# SmartHome.net
KiCad netlist of a schematic drawn in Altium Designer
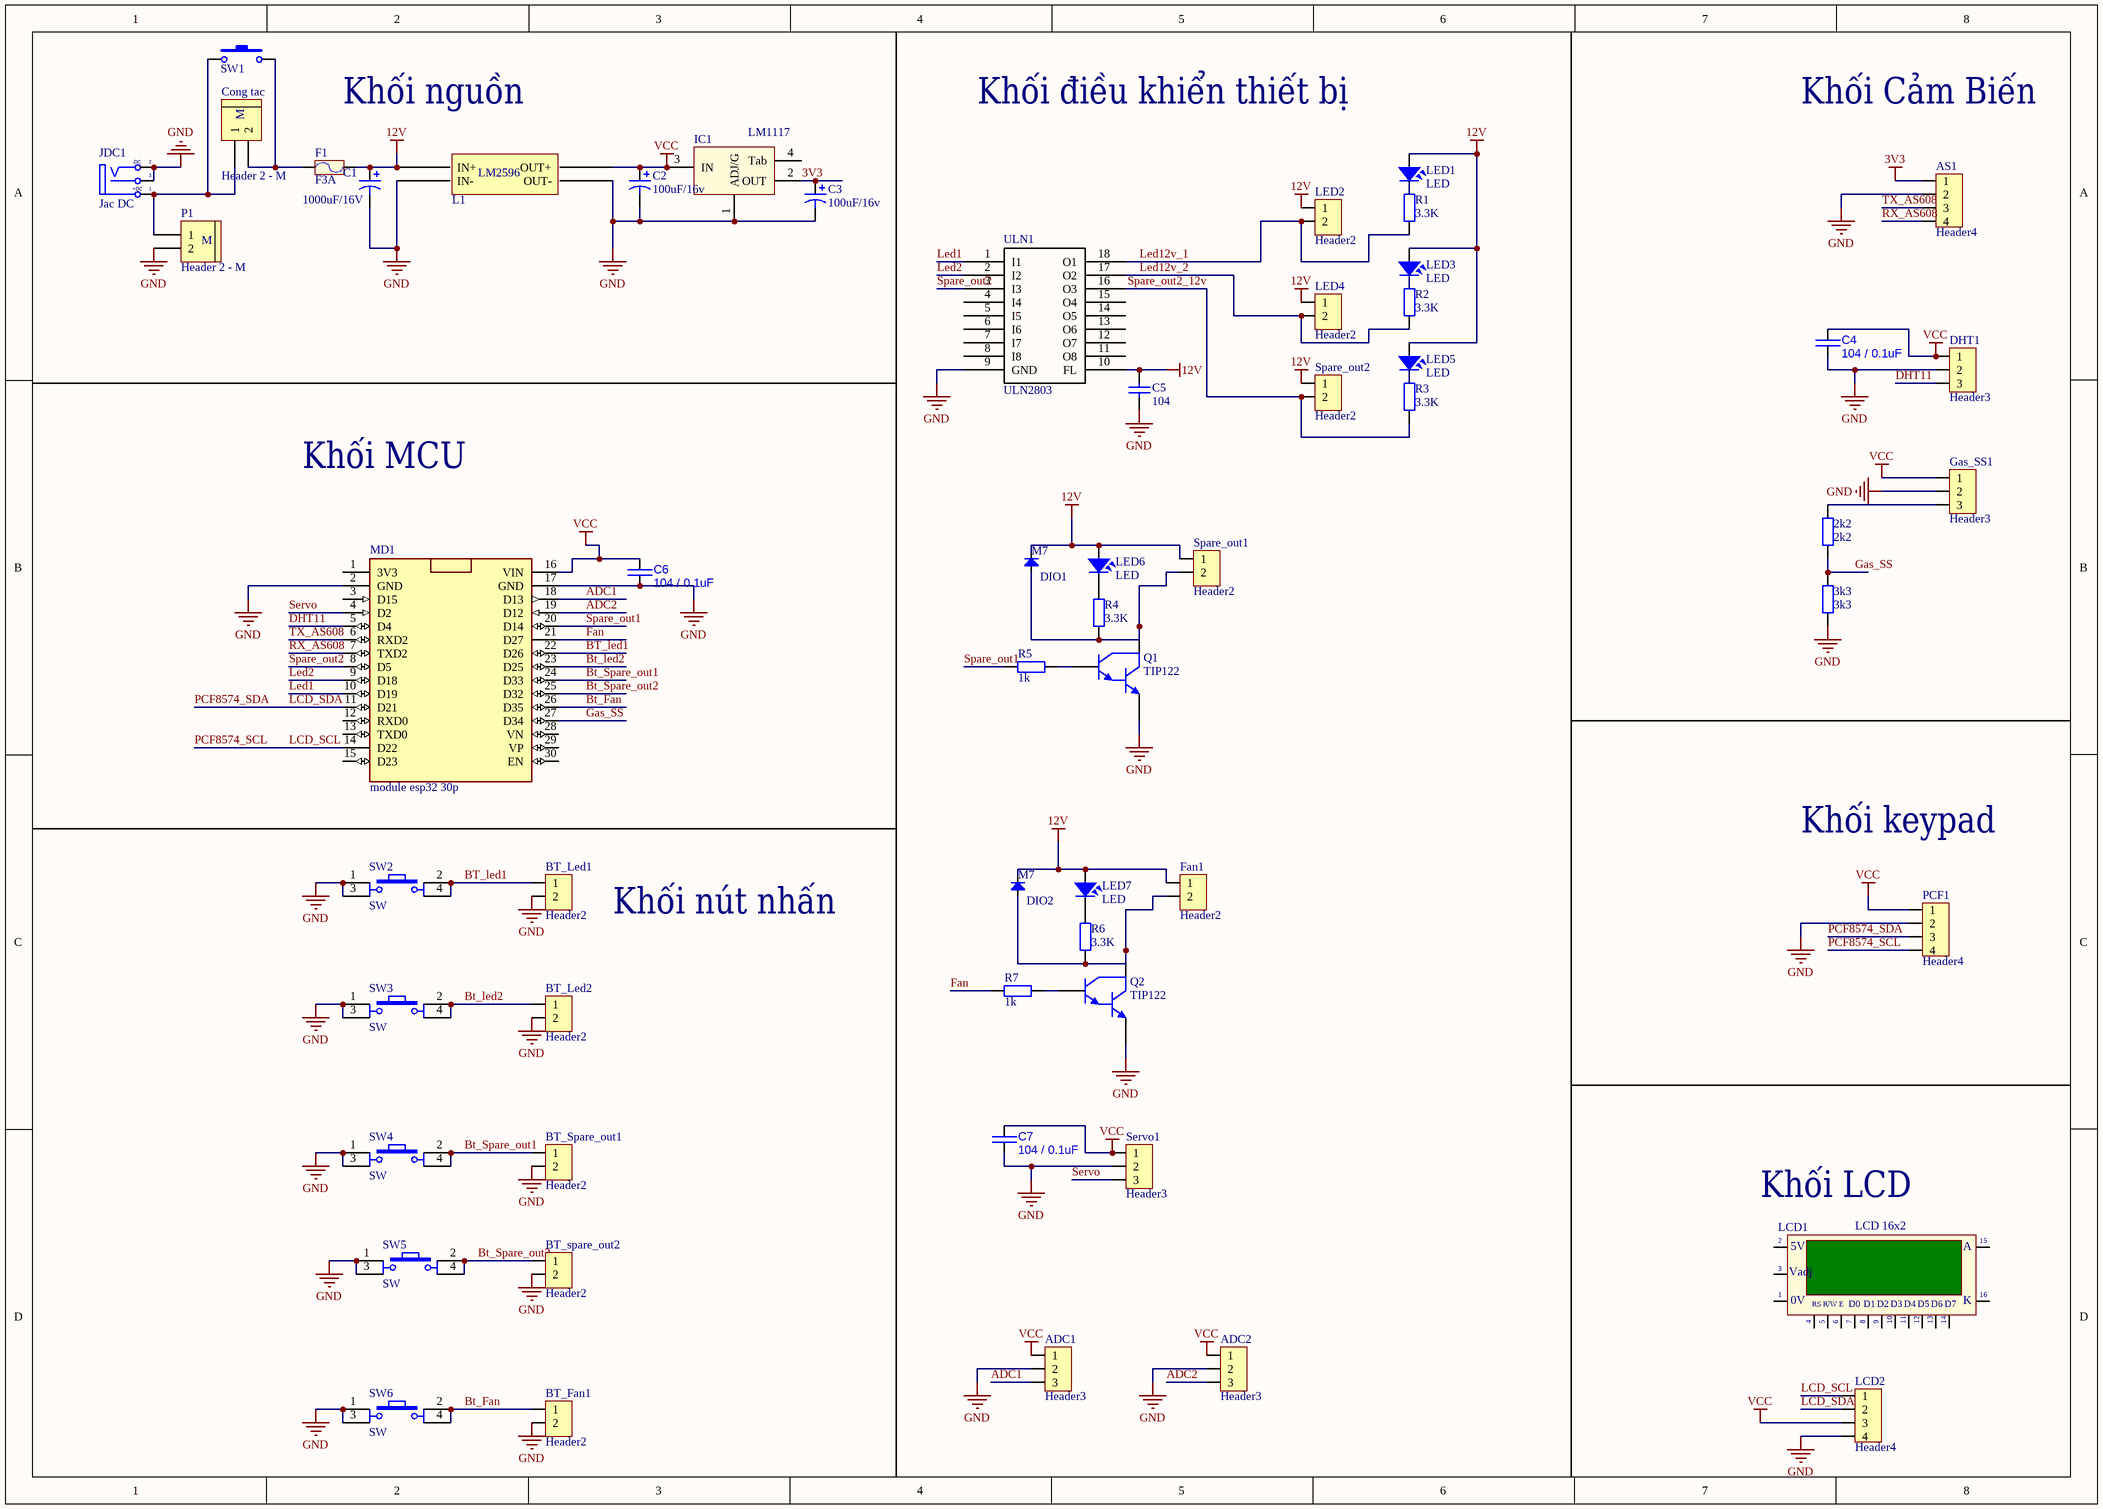
[diagram p0: SmartHome.SchDoc]

(export (version "E")
  (design (tool "Eeschema 10.0.6"))
  (components
    (comp (ref "2k2")
      (value "2k2")
      (footprint "DIEN TRO 0805")
      (description "Resistor SMD 0805")
      (fields (field (name "PUBLISHER") "Altium Limited"))
      (libsource (lib "My Library (1)") (part "R0805"))
    )
    (comp (ref "3k3")
      (value "3k3")
      (footprint "DIEN TRO 0805")
      (description "Resistor SMD 0805")
      (fields (field (name "PUBLISHER") "Altium Limited"))
      (libsource (lib "My Library (1)") (part "R0805"))
    )
    (comp (ref "ADC1")
      (value "Header3")
      (footprint "Header3")
      (description "Header IDC, 3 x 1 Pin Vertical 2.54mm Pitch (Non-Boxed, Male)")
      (fields
        (field (name "MANUFACTURER") "Würth Elektronik eiSos GmbH")
        (field (name "PARTNO") "613002143121")
        (field (name "CREATED BY") "Karrer Zheng")
      )
      (libsource (lib "My Library") (part "Header3"))
    )
    (comp (ref "ADC2")
      (value "Header3")
      (footprint "Header3")
      (description "Header IDC, 3 x 1 Pin Vertical 2.54mm Pitch (Non-Boxed, Male)")
      (fields
        (field (name "MANUFACTURER") "Würth Elektronik eiSos GmbH")
        (field (name "PARTNO") "613002143121")
        (field (name "CREATED BY") "Karrer Zheng")
      )
      (libsource (lib "My Library") (part "Header3"))
    )
    (comp (ref "AS1")
      (value "Header4")
      (footprint "Header4")
      (description "Header IDC, 4 x 1 Pin Vertical 2.54mm Pitch (Non-Boxed, Male)")
      (fields
        (field (name "MANUFACTURER") "Würth Elektronik eiSos GmbH")
        (field (name "PARTNO") "613002143121")
        (field (name "CREATED BY") "Karrer Zheng")
      )
      (libsource (lib "My Library") (part "Header4"))
    )
    (comp (ref "BT_Fan1")
      (value "Header2")
      (footprint "Header2")
      (description "Header IDC, 2 x 1 Pin Vertical 2.54mm Pitch (Non-Boxed, Male)")
      (fields
        (field (name "MANUFACTURER") "Würth Elektronik eiSos GmbH")
        (field (name "PARTNO") "613002143121")
        (field (name "CREATED BY") "Karrer Zheng")
      )
      (libsource (lib "My Library") (part "Header2"))
    )
    (comp (ref "BT_Led1")
      (value "Header2")
      (footprint "Header2")
      (description "Header IDC, 2 x 1 Pin Vertical 2.54mm Pitch (Non-Boxed, Male)")
      (fields
        (field (name "MANUFACTURER") "Würth Elektronik eiSos GmbH")
        (field (name "PARTNO") "613002143121")
        (field (name "CREATED BY") "Karrer Zheng")
      )
      (libsource (lib "My Library") (part "Header2"))
    )
    (comp (ref "BT_Led2")
      (value "Header2")
      (footprint "Header2")
      (description "Header IDC, 2 x 1 Pin Vertical 2.54mm Pitch (Non-Boxed, Male)")
      (fields
        (field (name "MANUFACTURER") "Würth Elektronik eiSos GmbH")
        (field (name "PARTNO") "613002143121")
        (field (name "CREATED BY") "Karrer Zheng")
      )
      (libsource (lib "My Library") (part "Header2"))
    )
    (comp (ref "BT_Spare_out1")
      (value "Header2")
      (footprint "Header2")
      (description "Header IDC, 2 x 1 Pin Vertical 2.54mm Pitch (Non-Boxed, Male)")
      (fields
        (field (name "MANUFACTURER") "Würth Elektronik eiSos GmbH")
        (field (name "PARTNO") "613002143121")
        (field (name "CREATED BY") "Karrer Zheng")
      )
      (libsource (lib "My Library") (part "Header2"))
    )
    (comp (ref "BT_spare_out2")
      (value "Header2")
      (footprint "Header2")
      (description "Header IDC, 2 x 1 Pin Vertical 2.54mm Pitch (Non-Boxed, Male)")
      (fields
        (field (name "MANUFACTURER") "Würth Elektronik eiSos GmbH")
        (field (name "PARTNO") "613002143121")
        (field (name "CREATED BY") "Karrer Zheng")
      )
      (libsource (lib "My Library") (part "Header2"))
    )
    (comp (ref "C1")
      (value "1000uF/16V")
      (footprint "C10mm")
      (description "Polarized Capacitor (Axial)")
      (fields (field (name "PUBLISHER") "Altium Limited"))
      (libsource (lib "My Library") (part "Cap Pol 12mm"))
    )
    (comp (ref "C2")
      (value "100uF/16v")
      (footprint "C5mm")
      (description "Polarized Capacitor (Axial)")
      (fields (field (name "PUBLISHER") "Altium Limited"))
      (libsource (lib "My Library") (part "Cap Pol 5mm"))
    )
    (comp (ref "C3")
      (value "100uF/16v")
      (footprint "C5mm")
      (description "Polarized Capacitor (Axial)")
      (fields (field (name "PUBLISHER") "Altium Limited"))
      (libsource (lib "My Library") (part "Cap Pol 5mm"))
    )
    (comp (ref "C4")
      (value "104 / 0.1uF")
      (footprint "CAP_0805")
      (description "Capacitor SMD Cer 1.8nF 10% 50V X7R 0805")
      (fields (field (name "TOLERANCE") "±10%") (field (name "Comment") "approved sub OK"))
      (libsource (lib "My library altium") (part "CAP C_0805"))
    )
    (comp (ref "C5")
      (value "104")
      (footprint "C0805")
      (description "Capacitor")
      (fields (field (name "PUBLISHER") "Altium Limited"))
      (libsource (lib "My Library") (part "CapSMD"))
    )
    (comp (ref "C6")
      (value "104 / 0.1uF")
      (footprint "CAP_0805")
      (description "Capacitor SMD Cer 1.8nF 10% 50V X7R 0805")
      (fields (field (name "TOLERANCE") "±10%") (field (name "Comment") "approved sub OK"))
      (libsource (lib "My library altium") (part "CAP C_0805"))
    )
    (comp (ref "C7")
      (value "104 / 0.1uF")
      (footprint "CAP_0805")
      (description "Capacitor SMD Cer 1.8nF 10% 50V X7R 0805")
      (fields (field (name "TOLERANCE") "±10%") (field (name "Comment") "approved sub OK"))
      (libsource (lib "My library altium") (part "CAP C_0805"))
    )
    (comp (ref "Cong tac")
      (value "Header 2 - M")
      (footprint "Medium - Header 2")
      (description "Header, 2-Pin, Medium")
      (fields (field (name "PUBLISHER") "Altium Limited"))
      (libsource (lib "My Library") (part "Header 2 - M"))
    )
    (comp (ref "DHT1")
      (value "Header3")
      (footprint "Header3")
      (description "Header IDC, 3 x 1 Pin Vertical 2.54mm Pitch (Non-Boxed, Male)")
      (fields
        (field (name "MANUFACTURER") "Würth Elektronik eiSos GmbH")
        (field (name "PARTNO") "613002143121")
        (field (name "CREATED BY") "Karrer Zheng")
      )
      (libsource (lib "My Library") (part "Header3"))
    )
    (comp (ref "DIO1")
      (value "M7")
      (footprint "DIO-SMD-106")
      (description "Default Diode")
      (fields (field (name "PUBLISHER") "Altium Limited"))
      (libsource (lib "My Library (1)") (part "Diode SMD"))
    )
    (comp (ref "DIO2")
      (value "M7")
      (footprint "DIO-SMD-106")
      (description "Default Diode")
      (fields (field (name "PUBLISHER") "Altium Limited"))
      (libsource (lib "My Library (1)") (part "Diode SMD"))
    )
    (comp (ref "F1")
      (value "F3A")
      (footprint "Fuse")
      (description "Fuse")
      (fields (field (name "DESIGNED BY") "VanDungEvn"))
      (libsource (lib "My Library") (part "Fuse"))
    )
    (comp (ref "Fan1")
      (value "Header2")
      (footprint "Header2")
      (description "Header IDC, 2 x 1 Pin Vertical 2.54mm Pitch (Non-Boxed, Male)")
      (fields
        (field (name "MANUFACTURER") "Würth Elektronik eiSos GmbH")
        (field (name "PARTNO") "613002143121")
        (field (name "CREATED BY") "Karrer Zheng")
      )
      (libsource (lib "My Library") (part "Header2"))
    )
    (comp (ref "Gas_SS1")
      (value "Header3")
      (footprint "Header3")
      (description "Header IDC, 3 x 1 Pin Vertical 2.54mm Pitch (Non-Boxed, Male)")
      (fields
        (field (name "MANUFACTURER") "Würth Elektronik eiSos GmbH")
        (field (name "PARTNO") "613002143121")
        (field (name "CREATED BY") "Karrer Zheng")
      )
      (libsource (lib "My Library") (part "Header3"))
    )
    (comp (ref "IC1")
      (value "LM1117")
      (footprint "SOT223-4N")
      (description "3v3")
      (libsource (lib "My Library") (part "LM1117"))
    )
    (comp (ref "JDC1")
      (value "Jac DC")
      (footprint "DC-IN")
      (description "Jac DC input")
      (libsource (lib "My Library") (part "DCIN"))
    )
    (comp (ref "L1")
      (value "BUCK_LM2596")
      (footprint "BUCK_LM2596")
      (libsource (lib "BUCK_LM2596_Sch") (part "BUCK_LM2596"))
    )
    (comp (ref "LCD1")
      (value "LCD 16x2")
      (footprint "LCD16X2N")
      (libsource (lib "My library altium") (part "LCD"))
    )
    (comp (ref "LCD2")
      (value "Header4")
      (footprint "XH2.54M-4")
      (description "Header IDC, 4 x 1 Pin Vertical 2.54mm Pitch (Non-Boxed, Male)")
      (fields
        (field (name "MANUFACTURER") "Würth Elektronik eiSos GmbH")
        (field (name "PARTNO") "613002143121")
        (field (name "CREATED BY") "Karrer Zheng")
      )
      (libsource (lib "My Library") (part "Header4"))
    )
    (comp (ref "LED1")
      (value "LED")
      (footprint "LED-5 GRe")
      (description "LED Single colour Green and Red")
      (libsource (lib "My Library") (part "LED"))
    )
    (comp (ref "LED2")
      (value "Header2")
      (footprint "Header2")
      (description "Header IDC, 2 x 1 Pin Vertical 2.54mm Pitch (Non-Boxed, Male)")
      (fields
        (field (name "MANUFACTURER") "Würth Elektronik eiSos GmbH")
        (field (name "PARTNO") "613002143121")
        (field (name "CREATED BY") "Karrer Zheng")
      )
      (libsource (lib "My Library") (part "Header2"))
    )
    (comp (ref "LED3")
      (value "LED")
      (footprint "LED-5 GRe")
      (description "LED Single colour Green and Red")
      (libsource (lib "My Library") (part "LED"))
    )
    (comp (ref "LED4")
      (value "Header2")
      (footprint "Header2")
      (description "Header IDC, 2 x 1 Pin Vertical 2.54mm Pitch (Non-Boxed, Male)")
      (fields
        (field (name "MANUFACTURER") "Würth Elektronik eiSos GmbH")
        (field (name "PARTNO") "613002143121")
        (field (name "CREATED BY") "Karrer Zheng")
      )
      (libsource (lib "My Library") (part "Header2"))
    )
    (comp (ref "LED5")
      (value "LED")
      (footprint "LED-5 GRe")
      (description "LED Single colour Green and Red")
      (libsource (lib "My Library") (part "LED"))
    )
    (comp (ref "LED6")
      (value "LED")
      (footprint "LED-5 GRe")
      (description "LED Single colour Green and Red")
      (libsource (lib "My Library") (part "LED"))
    )
    (comp (ref "LED7")
      (value "LED")
      (footprint "LED-5 GRe")
      (description "LED Single colour Green and Red")
      (libsource (lib "My Library") (part "LED"))
    )
    (comp (ref "MD1")
      (value "module esp32 30p")
      (footprint "module esp32 30 pin")
      (libsource (lib "Chuong Engineer") (part "module esp32 30p"))
    )
    (comp (ref "P1")
      (value "Header 2 - M")
      (footprint "Medium - Header 2")
      (description "Header, 2-Pin, Medium")
      (fields (field (name "PUBLISHER") "Altium Limited"))
      (libsource (lib "") (part "Header 2 - M_1"))
    )
    (comp (ref "PCF1")
      (value "Header4")
      (footprint "XH2.54M-4")
      (description "Header IDC, 4 x 1 Pin Vertical 2.54mm Pitch (Non-Boxed, Male)")
      (fields
        (field (name "MANUFACTURER") "Würth Elektronik eiSos GmbH")
        (field (name "PARTNO") "613002143121")
        (field (name "CREATED BY") "Karrer Zheng")
      )
      (libsource (lib "My Library") (part "Header4"))
    )
    (comp (ref "Q1")
      (value "TIP122")
      (footprint "QTO-220")
      (description "Darlington Silicon Power NPN Transistor, 8 Amp, 100 Volts and 65 Watts")
      (libsource (lib "My Library (1)") (part "TIP122"))
    )
    (comp (ref "Q2")
      (value "TIP122")
      (footprint "QTO-220")
      (description "Darlington Silicon Power NPN Transistor, 8 Amp, 100 Volts and 65 Watts")
      (libsource (lib "My Library (1)") (part "TIP122"))
    )
    (comp (ref "R1")
      (value "3.3K")
      (footprint "DIEN TRO 0805")
      (description "Resistor SMD 0805")
      (fields (field (name "PUBLISHER") "Altium Limited"))
      (libsource (lib "My Library (1)") (part "R0805"))
    )
    (comp (ref "R2")
      (value "3.3K")
      (footprint "DIEN TRO 0805")
      (description "Resistor SMD 0805")
      (fields (field (name "PUBLISHER") "Altium Limited"))
      (libsource (lib "My Library (1)") (part "R0805"))
    )
    (comp (ref "R3")
      (value "3.3K")
      (footprint "DIEN TRO 0805")
      (description "Resistor SMD 0805")
      (fields (field (name "PUBLISHER") "Altium Limited"))
      (libsource (lib "My Library (1)") (part "R0805"))
    )
    (comp (ref "R4")
      (value "3.3K")
      (footprint "DIEN TRO 0805")
      (description "Resistor SMD 0805")
      (fields (field (name "PUBLISHER") "Altium Limited"))
      (libsource (lib "My Library (1)") (part "R0805"))
    )
    (comp (ref "R5")
      (value "1k")
      (footprint "DIEN TRO 0805")
      (description "Resistor SMD 0805")
      (fields (field (name "PUBLISHER") "Altium Limited"))
      (libsource (lib "") (part "R0805_1"))
    )
    (comp (ref "R6")
      (value "3.3K")
      (footprint "DIEN TRO 0805")
      (description "Resistor SMD 0805")
      (fields (field (name "PUBLISHER") "Altium Limited"))
      (libsource (lib "My Library (1)") (part "R0805"))
    )
    (comp (ref "R7")
      (value "1k")
      (footprint "DIEN TRO 0805")
      (description "Resistor SMD 0805")
      (fields (field (name "PUBLISHER") "Altium Limited"))
      (libsource (lib "") (part "R0805_1"))
    )
    (comp (ref "Servo1")
      (value "Header3")
      (footprint "Header3")
      (description "Header IDC, 3 x 1 Pin Vertical 2.54mm Pitch (Non-Boxed, Male)")
      (fields
        (field (name "MANUFACTURER") "Würth Elektronik eiSos GmbH")
        (field (name "PARTNO") "613002143121")
        (field (name "CREATED BY") "Karrer Zheng")
      )
      (libsource (lib "My Library") (part "Header3"))
    )
    (comp (ref "Spare_out1")
      (value "Header2")
      (footprint "Header2")
      (description "Header IDC, 2 x 1 Pin Vertical 2.54mm Pitch (Non-Boxed, Male)")
      (fields
        (field (name "MANUFACTURER") "Würth Elektronik eiSos GmbH")
        (field (name "PARTNO") "613002143121")
        (field (name "CREATED BY") "Karrer Zheng")
      )
      (libsource (lib "My Library") (part "Header2"))
    )
    (comp (ref "Spare_out2")
      (value "Header2")
      (footprint "Header2")
      (description "Header IDC, 2 x 1 Pin Vertical 2.54mm Pitch (Non-Boxed, Male)")
      (fields
        (field (name "MANUFACTURER") "Würth Elektronik eiSos GmbH")
        (field (name "PARTNO") "613002143121")
        (field (name "CREATED BY") "Karrer Zheng")
      )
      (libsource (lib "My Library") (part "Header2"))
    )
    (comp (ref "SW1")
      (value "KCD01-11_SWITCH")
      (footprint "KCD01-11")
      (description "Nut Nhan 2 Chan SMD 3x6x2.5")
      (libsource (lib "KS Chuong") (part "KCD01-11_SWITCH"))
    )
    (comp (ref "SW2")
      (value "SW")
      (footprint "SW4")
      (description "Switch button 4 pin")
      (libsource (lib "My Library (1)") (part "SW4"))
    )
    (comp (ref "SW3")
      (value "SW")
      (footprint "SW4")
      (description "Switch button 4 pin")
      (libsource (lib "My Library (1)") (part "SW4"))
    )
    (comp (ref "SW4")
      (value "SW")
      (footprint "SW4")
      (description "Switch button 4 pin")
      (libsource (lib "My Library (1)") (part "SW4"))
    )
    (comp (ref "SW5")
      (value "SW")
      (footprint "SW4")
      (description "Switch button 4 pin")
      (libsource (lib "My Library (1)") (part "SW4"))
    )
    (comp (ref "SW6")
      (value "SW")
      (footprint "SW4")
      (description "Switch button 4 pin")
      (libsource (lib "My Library (1)") (part "SW4"))
    )
    (comp (ref "ULN1")
      (value "ULN2803")
      (footprint "DIP18/W0.3")
      (description "OCTAL HIGH CURRENT DRIVER")
      (fields
        (field (name "MANUFACTURER") "Texas Instruments")
        (field (name "MANUFACTURER PART NUMBER") "ULN2803ADWR")
      )
      (libsource (lib "My Library") (part "ULN2803"))
    )
  )
  (nets
    (net (code "1") (name "/ADC1") (class "Default")
      (node (ref "ADC1") (pin "3") (pinfunction "3_3") (pintype "passive"))
      (node (ref "MD1") (pin "18") (pinfunction "D13_18") (pintype "output"))
    )
    (net (code "2") (name "/ADC2") (class "Default")
      (node (ref "ADC2") (pin "3") (pinfunction "3_3") (pintype "passive"))
      (node (ref "MD1") (pin "19") (pinfunction "D12_19") (pintype "input"))
    )
    (net (code "3") (name "/BT_led1") (class "Default")
      (node (ref "BT_Led1") (pin "1") (pinfunction "1_1") (pintype "passive"))
      (node (ref "MD1") (pin "22") (pinfunction "D26_22") (pintype "bidirectional"))
      (node (ref "SW2") (pin "2") (pintype "passive"))
      (node (ref "SW2") (pin "4") (pintype "passive"))
    )
    (net (code "4") (name "/Bt_Fan") (class "Default")
      (node (ref "BT_Fan1") (pin "1") (pinfunction "1_1") (pintype "passive"))
      (node (ref "MD1") (pin "26") (pinfunction "D35_26") (pintype "bidirectional"))
      (node (ref "SW6") (pin "2") (pintype "passive"))
      (node (ref "SW6") (pin "4") (pintype "passive"))
    )
    (net (code "5") (name "/Bt_Spare_out1") (class "Default")
      (node (ref "BT_Spare_out1") (pin "1") (pinfunction "1_1") (pintype "passive"))
      (node (ref "MD1") (pin "24") (pinfunction "D33_24") (pintype "bidirectional"))
      (node (ref "SW4") (pin "2") (pintype "passive"))
      (node (ref "SW4") (pin "4") (pintype "passive"))
    )
    (net (code "6") (name "/Bt_Spare_out2") (class "Default")
      (node (ref "BT_spare_out2") (pin "1") (pinfunction "1_1") (pintype "passive"))
      (node (ref "MD1") (pin "25") (pinfunction "D32_25") (pintype "bidirectional"))
      (node (ref "SW5") (pin "2") (pintype "passive"))
      (node (ref "SW5") (pin "4") (pintype "passive"))
    )
    (net (code "7") (name "/Bt_led2") (class "Default")
      (node (ref "BT_Led2") (pin "1") (pinfunction "1_1") (pintype "passive"))
      (node (ref "MD1") (pin "23") (pinfunction "D25_23") (pintype "bidirectional"))
      (node (ref "SW3") (pin "2") (pintype "passive"))
      (node (ref "SW3") (pin "4") (pintype "passive"))
    )
    (net (code "8") (name "/DHT11") (class "Default")
      (node (ref "DHT1") (pin "3") (pinfunction "3_3") (pintype "passive"))
      (node (ref "MD1") (pin "5") (pinfunction "D4_5") (pintype "bidirectional"))
    )
    (net (code "9") (name "/Fan") (class "Default")
      (node (ref "MD1") (pin "21") (pinfunction "D27_21") (pintype "power_in"))
      (node (ref "R7") (pin "2") (pinfunction "2_2") (pintype "passive"))
    )
    (net (code "10") (name "/Gas_SS") (class "Default")
      (node (ref "2k2") (pin "2") (pinfunction "2_2") (pintype "passive"))
      (node (ref "3k3") (pin "1") (pinfunction "1_1") (pintype "passive"))
      (node (ref "MD1") (pin "27") (pinfunction "D34_27") (pintype "bidirectional"))
    )
    (net (code "11") (name "/LCD_SCL") (class "Default")
      (node (ref "LCD2") (pin "1") (pinfunction "1_1") (pintype "passive"))
      (node (ref "MD1") (pin "14") (pinfunction "D22_14") (pintype "power_in"))
      (node (ref "PCF1") (pin "4") (pinfunction "4_4") (pintype "passive"))
    )
    (net (code "12") (name "/LCD_SDA") (class "Default")
      (node (ref "LCD2") (pin "2") (pinfunction "2_2") (pintype "passive"))
      (node (ref "MD1") (pin "11") (pinfunction "D21_11") (pintype "bidirectional"))
      (node (ref "PCF1") (pin "3") (pinfunction "3_3") (pintype "passive"))
    )
    (net (code "13") (name "/Led1") (class "Default")
      (node (ref "MD1") (pin "10") (pinfunction "D19_10") (pintype "bidirectional"))
      (node (ref "ULN1") (pin "1") (pinfunction "I1_1") (pintype "passive"))
    )
    (net (code "14") (name "/Led2") (class "Default")
      (node (ref "MD1") (pin "9") (pinfunction "D18_9") (pintype "bidirectional"))
      (node (ref "ULN1") (pin "2") (pinfunction "I2_2") (pintype "passive"))
    )
    (net (code "15") (name "/Led12v_1") (class "Default")
      (node (ref "LED2") (pin "2") (pinfunction "2_2") (pintype "passive"))
      (node (ref "R1") (pin "2") (pinfunction "2_2") (pintype "passive"))
      (node (ref "ULN1") (pin "18") (pinfunction "O1_18") (pintype "passive"))
    )
    (net (code "16") (name "/Led12v_2") (class "Default")
      (node (ref "LED4") (pin "2") (pinfunction "2_2") (pintype "passive"))
      (node (ref "R2") (pin "2") (pinfunction "2_2") (pintype "passive"))
      (node (ref "ULN1") (pin "17") (pinfunction "O2_17") (pintype "passive"))
    )
    (net (code "17") (name "/RX_AS608") (class "Default")
      (node (ref "AS1") (pin "4") (pinfunction "4_4") (pintype "passive"))
      (node (ref "MD1") (pin "7") (pinfunction "TXD2_7") (pintype "bidirectional"))
    )
    (net (code "18") (name "/Servo") (class "Default")
      (node (ref "MD1") (pin "4") (pinfunction "D2_4") (pintype "input"))
      (node (ref "Servo1") (pin "3") (pinfunction "3_3") (pintype "passive"))
    )
    (net (code "19") (name "/Spare_out1") (class "Default")
      (node (ref "MD1") (pin "20") (pinfunction "D14_20") (pintype "bidirectional"))
      (node (ref "R5") (pin "2") (pinfunction "2_2") (pintype "passive"))
    )
    (net (code "20") (name "/Spare_out2") (class "Default")
      (node (ref "MD1") (pin "8") (pinfunction "D5_8") (pintype "bidirectional"))
      (node (ref "ULN1") (pin "3") (pinfunction "I3_3") (pintype "passive"))
    )
    (net (code "21") (name "/Spare_out2_12v") (class "Default")
      (node (ref "R3") (pin "2") (pinfunction "2_2") (pintype "passive"))
      (node (ref "Spare_out2") (pin "2") (pinfunction "2_2") (pintype "passive"))
      (node (ref "ULN1") (pin "16") (pinfunction "O3_16") (pintype "passive"))
    )
    (net (code "22") (name "/TX_AS608") (class "Default")
      (node (ref "AS1") (pin "3") (pinfunction "3_3") (pintype "passive"))
      (node (ref "MD1") (pin "6") (pinfunction "RXD2_6") (pintype "bidirectional"))
    )
    (net (code "23") (name "3V3") (class "Default")
      (node (ref "AS1") (pin "1") (pinfunction "1_1") (pintype "passive"))
      (node (ref "C3") (pin "1") (pinfunction "1_1") (pintype "passive"))
      (node (ref "IC1") (pin "2") (pinfunction "OUT_2") (pintype "passive"))
    )
    (net (code "24") (name "12V") (class "Default")
      (node (ref "C1") (pin "1") (pinfunction "1_1") (pintype "passive"))
      (node (ref "C5") (pin "1") (pinfunction "1_1") (pintype "passive"))
      (node (ref "DIO1") (pin "2") (pinfunction "K_2") (pintype "passive"))
      (node (ref "DIO2") (pin "2") (pinfunction "K_2") (pintype "passive"))
      (node (ref "F1") (pin "2") (pinfunction "2_2") (pintype "passive"))
      (node (ref "Fan1") (pin "1") (pinfunction "1_1") (pintype "passive"))
      (node (ref "L1") (pin "1") (pinfunction "IN+_1") (pintype "passive"))
      (node (ref "LED1") (pin "1") (pinfunction "1_1") (pintype "passive"))
      (node (ref "LED2") (pin "1") (pinfunction "1_1") (pintype "passive"))
      (node (ref "LED3") (pin "1") (pinfunction "1_1") (pintype "passive"))
      (node (ref "LED4") (pin "1") (pinfunction "1_1") (pintype "passive"))
      (node (ref "LED5") (pin "1") (pinfunction "1_1") (pintype "passive"))
      (node (ref "LED6") (pin "1") (pinfunction "1_1") (pintype "passive"))
      (node (ref "LED7") (pin "1") (pinfunction "1_1") (pintype "passive"))
      (node (ref "Spare_out1") (pin "1") (pinfunction "1_1") (pintype "passive"))
      (node (ref "Spare_out2") (pin "1") (pinfunction "1_1") (pintype "passive"))
      (node (ref "ULN1") (pin "10") (pinfunction "FL_10") (pintype "passive"))
    )
    (net (code "25") (name "GND") (class "Default")
      (node (ref "3k3") (pin "2") (pinfunction "2_2") (pintype "passive"))
      (node (ref "ADC1") (pin "2") (pinfunction "2_2") (pintype "passive"))
      (node (ref "ADC2") (pin "2") (pinfunction "2_2") (pintype "passive"))
      (node (ref "AS1") (pin "2") (pinfunction "2_2") (pintype "passive"))
      (node (ref "BT_Fan1") (pin "2") (pinfunction "2_2") (pintype "passive"))
      (node (ref "BT_Led1") (pin "2") (pinfunction "2_2") (pintype "passive"))
      (node (ref "BT_Led2") (pin "2") (pinfunction "2_2") (pintype "passive"))
      (node (ref "BT_Spare_out1") (pin "2") (pinfunction "2_2") (pintype "passive"))
      (node (ref "BT_spare_out2") (pin "2") (pinfunction "2_2") (pintype "passive"))
      (node (ref "C1") (pin "2") (pinfunction "2_2") (pintype "passive"))
      (node (ref "C2") (pin "2") (pinfunction "2_2") (pintype "passive"))
      (node (ref "C3") (pin "2") (pinfunction "2_2") (pintype "passive"))
      (node (ref "C4") (pin "1") (pintype "passive"))
      (node (ref "C5") (pin "2") (pinfunction "2_2") (pintype "passive"))
      (node (ref "C6") (pin "1") (pintype "passive"))
      (node (ref "C7") (pin "1") (pintype "passive"))
      (node (ref "DHT1") (pin "2") (pinfunction "2_2") (pintype "passive"))
      (node (ref "Gas_SS1") (pin "2") (pinfunction "2_2") (pintype "passive"))
      (node (ref "IC1") (pin "1") (pinfunction "ADJ/G_1") (pintype "passive"))
      (node (ref "JDC1") (pin "2") (pinfunction "TN_2") (pintype "passive"))
      (node (ref "JDC1") (pin "3") (pinfunction "S_3") (pintype "power_in"))
      (node (ref "L1") (pin "2") (pinfunction "IN-_2") (pintype "passive"))
      (node (ref "L1") (pin "3") (pinfunction "OUT-_3") (pintype "passive"))
      (node (ref "LCD2") (pin "4") (pinfunction "4_4") (pintype "passive"))
      (node (ref "MD1") (pin "17") (pinfunction "GND_17") (pintype "power_in"))
      (node (ref "MD1") (pin "2") (pinfunction "GND_2") (pintype "power_in"))
      (node (ref "P1") (pin "2") (pinfunction "2_2") (pintype "passive"))
      (node (ref "PCF1") (pin "2") (pinfunction "2_2") (pintype "passive"))
      (node (ref "Q1") (pin "3") (pinfunction "E_3") (pintype "passive"))
      (node (ref "Q2") (pin "3") (pinfunction "E_3") (pintype "passive"))
      (node (ref "SW2") (pin "1") (pintype "passive"))
      (node (ref "SW2") (pin "3") (pintype "passive"))
      (node (ref "SW3") (pin "1") (pintype "passive"))
      (node (ref "SW3") (pin "3") (pintype "passive"))
      (node (ref "SW4") (pin "1") (pintype "passive"))
      (node (ref "SW4") (pin "3") (pintype "passive"))
      (node (ref "SW5") (pin "1") (pintype "passive"))
      (node (ref "SW5") (pin "3") (pintype "passive"))
      (node (ref "SW6") (pin "1") (pintype "passive"))
      (node (ref "SW6") (pin "3") (pintype "passive"))
      (node (ref "Servo1") (pin "2") (pinfunction "2_2") (pintype "passive"))
      (node (ref "ULN1") (pin "9") (pinfunction "GND_9") (pintype "passive"))
    )
    (net (code "26") (name "Net-(2k2-Pad1)") (class "Default")
      (node (ref "2k2") (pin "1") (pinfunction "1_1") (pintype "passive"))
      (node (ref "Gas_SS1") (pin "3") (pinfunction "3_3") (pintype "passive"))
    )
    (net (code "27") (name "Net-(Cong tac-Pad2)") (class "Default")
      (node (ref "Cong tac") (pin "2") (pinfunction "2_2") (pintype "passive"))
      (node (ref "F1") (pin "1") (pinfunction "1_1") (pintype "passive"))
      (node (ref "SW1") (pin "2") (pinfunction "2_2") (pintype "passive"))
    )
    (net (code "28") (name "Net-(DIO1-A)") (class "Default")
      (node (ref "DIO1") (pin "1") (pinfunction "A_1") (pintype "passive"))
      (node (ref "Q1") (pin "2") (pinfunction "C_2") (pintype "passive"))
      (node (ref "R4") (pin "2") (pinfunction "2_2") (pintype "passive"))
      (node (ref "Spare_out1") (pin "2") (pinfunction "2_2") (pintype "passive"))
    )
    (net (code "29") (name "Net-(DIO2-A)") (class "Default")
      (node (ref "DIO2") (pin "1") (pinfunction "A_1") (pintype "passive"))
      (node (ref "Fan1") (pin "2") (pinfunction "2_2") (pintype "passive"))
      (node (ref "Q2") (pin "2") (pinfunction "C_2") (pintype "passive"))
      (node (ref "R6") (pin "2") (pinfunction "2_2") (pintype "passive"))
    )
    (net (code "30") (name "Net-(JDC1-T)") (class "Default")
      (node (ref "Cong tac") (pin "1") (pinfunction "1_1") (pintype "passive"))
      (node (ref "JDC1") (pin "1") (pinfunction "T_1") (pintype "passive"))
      (node (ref "P1") (pin "1") (pinfunction "1_1") (pintype "passive"))
      (node (ref "SW1") (pin "1") (pinfunction "1_1") (pintype "passive"))
    )
    (net (code "31") (name "Net-(LED1-Pad2)") (class "Default")
      (node (ref "LED1") (pin "2") (pinfunction "2_2") (pintype "passive"))
      (node (ref "R1") (pin "1") (pinfunction "1_1") (pintype "passive"))
    )
    (net (code "32") (name "Net-(LED3-Pad2)") (class "Default")
      (node (ref "LED3") (pin "2") (pinfunction "2_2") (pintype "passive"))
      (node (ref "R2") (pin "1") (pinfunction "1_1") (pintype "passive"))
    )
    (net (code "33") (name "Net-(LED5-Pad2)") (class "Default")
      (node (ref "LED5") (pin "2") (pinfunction "2_2") (pintype "passive"))
      (node (ref "R3") (pin "1") (pinfunction "1_1") (pintype "passive"))
    )
    (net (code "34") (name "Net-(LED6-Pad2)") (class "Default")
      (node (ref "LED6") (pin "2") (pinfunction "2_2") (pintype "passive"))
      (node (ref "R4") (pin "1") (pinfunction "1_1") (pintype "passive"))
    )
    (net (code "35") (name "Net-(LED7-Pad2)") (class "Default")
      (node (ref "LED7") (pin "2") (pinfunction "2_2") (pintype "passive"))
      (node (ref "R6") (pin "1") (pinfunction "1_1") (pintype "passive"))
    )
    (net (code "36") (name "Net-(Q1-B)") (class "Default")
      (node (ref "Q1") (pin "1") (pinfunction "B_1") (pintype "passive"))
      (node (ref "R5") (pin "1") (pinfunction "1_1") (pintype "passive"))
    )
    (net (code "37") (name "Net-(Q2-B)") (class "Default")
      (node (ref "Q2") (pin "1") (pinfunction "B_1") (pintype "passive"))
      (node (ref "R7") (pin "1") (pinfunction "1_1") (pintype "passive"))
    )
    (net (code "38") (name "VCC") (class "Default")
      (node (ref "ADC1") (pin "1") (pinfunction "1_1") (pintype "passive"))
      (node (ref "ADC2") (pin "1") (pinfunction "1_1") (pintype "passive"))
      (node (ref "C2") (pin "1") (pinfunction "1_1") (pintype "passive"))
      (node (ref "C4") (pin "2") (pintype "passive"))
      (node (ref "C6") (pin "2") (pintype "passive"))
      (node (ref "C7") (pin "2") (pintype "passive"))
      (node (ref "DHT1") (pin "1") (pinfunction "1_1") (pintype "passive"))
      (node (ref "Gas_SS1") (pin "1") (pinfunction "1_1") (pintype "passive"))
      (node (ref "IC1") (pin "3") (pinfunction "IN_3") (pintype "passive"))
      (node (ref "L1") (pin "4") (pinfunction "OUT+_4") (pintype "passive"))
      (node (ref "LCD2") (pin "3") (pinfunction "3_3") (pintype "passive"))
      (node (ref "MD1") (pin "16") (pinfunction "VIN_16") (pintype "power_in"))
      (node (ref "PCF1") (pin "1") (pinfunction "1_1") (pintype "passive"))
      (node (ref "Servo1") (pin "1") (pinfunction "1_1") (pintype "passive"))
    )
    (net (code "39") (name "unconnected-(IC1-Tab-Pad4)") (class "Default")
      (node (ref "IC1") (pin "4") (pinfunction "Tab_4") (pintype "passive"))
    )
    (net (code "40") (name "unconnected-(LCD1-A-Pad15)") (class "Default")
      (node (ref "LCD1") (pin "15") (pinfunction "A_15") (pintype "passive"))
    )
    (net (code "41") (name "unconnected-(LCD1-D0-Pad7)") (class "Default")
      (node (ref "LCD1") (pin "7") (pinfunction "D0_7") (pintype "passive"))
    )
    (net (code "42") (name "unconnected-(LCD1-D1-Pad8)") (class "Default")
      (node (ref "LCD1") (pin "8") (pinfunction "D1_8") (pintype "passive"))
    )
    (net (code "43") (name "unconnected-(LCD1-D2-Pad9)") (class "Default")
      (node (ref "LCD1") (pin "9") (pinfunction "D2_9") (pintype "passive"))
    )
    (net (code "44") (name "unconnected-(LCD1-D3-Pad10)") (class "Default")
      (node (ref "LCD1") (pin "10") (pinfunction "D3_10") (pintype "passive"))
    )
    (net (code "45") (name "unconnected-(LCD1-D4-Pad11)") (class "Default")
      (node (ref "LCD1") (pin "11") (pinfunction "D4_11") (pintype "passive"))
    )
    (net (code "46") (name "unconnected-(LCD1-D5-Pad12)") (class "Default")
      (node (ref "LCD1") (pin "12") (pinfunction "D5_12") (pintype "passive"))
    )
    (net (code "47") (name "unconnected-(LCD1-D6-Pad13)") (class "Default")
      (node (ref "LCD1") (pin "13") (pinfunction "D6_13") (pintype "passive"))
    )
    (net (code "48") (name "unconnected-(LCD1-D7-Pad14)") (class "Default")
      (node (ref "LCD1") (pin "14") (pinfunction "D7_14") (pintype "passive"))
    )
    (net (code "49") (name "unconnected-(LCD1-GND-Pad1)") (class "Default")
      (node (ref "LCD1") (pin "1") (pinfunction "GND_1") (pintype "passive"))
    )
    (net (code "50") (name "unconnected-(LCD1-K-Pad16)") (class "Default")
      (node (ref "LCD1") (pin "16") (pinfunction "K_16") (pintype "passive"))
    )
    (net (code "51") (name "unconnected-(LCD1-RS-Pad4)") (class "Default")
      (node (ref "LCD1") (pin "4") (pinfunction "RS_4") (pintype "passive"))
    )
    (net (code "52") (name "unconnected-(LCD1-R{slash}~{W}-Pad5)") (class "Default")
      (node (ref "LCD1") (pin "5") (pinfunction "R/~{W}_5") (pintype "passive"))
    )
    (net (code "53") (name "unconnected-(LCD1-VAdj-Pad3)") (class "Default")
      (node (ref "LCD1") (pin "3") (pinfunction "VAdj_3") (pintype "passive"))
    )
    (net (code "54") (name "unconnected-(LCD1-VDD-Pad2)") (class "Default")
      (node (ref "LCD1") (pin "2") (pinfunction "VDD_2") (pintype "passive"))
    )
    (net (code "55") (name "unconnected-(LCD1-~{EN}-Pad6)") (class "Default")
      (node (ref "LCD1") (pin "6") (pinfunction "~{EN}_6") (pintype "passive"))
    )
    (net (code "56") (name "unconnected-(MD1-3V3-Pad1)") (class "Default")
      (node (ref "MD1") (pin "1") (pinfunction "3V3_1") (pintype "power_in"))
    )
    (net (code "57") (name "unconnected-(MD1-D15-Pad3)") (class "Default")
      (node (ref "MD1") (pin "3") (pinfunction "D15_3") (pintype "input"))
    )
    (net (code "58") (name "unconnected-(MD1-D23-Pad15)") (class "Default")
      (node (ref "MD1") (pin "15") (pinfunction "D23_15") (pintype "bidirectional"))
    )
    (net (code "59") (name "unconnected-(MD1-EN-Pad30)") (class "Default")
      (node (ref "MD1") (pin "30") (pinfunction "EN_30") (pintype "bidirectional"))
    )
    (net (code "60") (name "unconnected-(MD1-RXD0-Pad12)") (class "Default")
      (node (ref "MD1") (pin "12") (pinfunction "RXD0_12") (pintype "bidirectional"))
    )
    (net (code "61") (name "unconnected-(MD1-TXD0-Pad13)") (class "Default")
      (node (ref "MD1") (pin "13") (pinfunction "TXD0_13") (pintype "bidirectional"))
    )
    (net (code "62") (name "unconnected-(MD1-VN-Pad28)") (class "Default")
      (node (ref "MD1") (pin "28") (pinfunction "VN_28") (pintype "bidirectional"))
    )
    (net (code "63") (name "unconnected-(MD1-VP-Pad29)") (class "Default")
      (node (ref "MD1") (pin "29") (pinfunction "VP_29") (pintype "bidirectional"))
    )
    (net (code "64") (name "unconnected-(ULN1-I4-Pad4)") (class "Default")
      (node (ref "ULN1") (pin "4") (pinfunction "I4_4") (pintype "passive"))
    )
    (net (code "65") (name "unconnected-(ULN1-I5-Pad5)") (class "Default")
      (node (ref "ULN1") (pin "5") (pinfunction "I5_5") (pintype "passive"))
    )
    (net (code "66") (name "unconnected-(ULN1-I6-Pad6)") (class "Default")
      (node (ref "ULN1") (pin "6") (pinfunction "I6_6") (pintype "passive"))
    )
    (net (code "67") (name "unconnected-(ULN1-I7-Pad7)") (class "Default")
      (node (ref "ULN1") (pin "7") (pinfunction "I7_7") (pintype "passive"))
    )
    (net (code "68") (name "unconnected-(ULN1-I8-Pad8)") (class "Default")
      (node (ref "ULN1") (pin "8") (pinfunction "I8_8") (pintype "passive"))
    )
    (net (code "69") (name "unconnected-(ULN1-O4-Pad15)") (class "Default")
      (node (ref "ULN1") (pin "15") (pinfunction "O4_15") (pintype "passive"))
    )
    (net (code "70") (name "unconnected-(ULN1-O5-Pad14)") (class "Default")
      (node (ref "ULN1") (pin "14") (pinfunction "O5_14") (pintype "passive"))
    )
    (net (code "71") (name "unconnected-(ULN1-O6-Pad13)") (class "Default")
      (node (ref "ULN1") (pin "13") (pinfunction "O6_13") (pintype "passive"))
    )
    (net (code "72") (name "unconnected-(ULN1-O7-Pad12)") (class "Default")
      (node (ref "ULN1") (pin "12") (pinfunction "O7_12") (pintype "passive"))
    )
    (net (code "73") (name "unconnected-(ULN1-O8-Pad11)") (class "Default")
      (node (ref "ULN1") (pin "11") (pinfunction "O8_11") (pintype "passive"))
    )
  )
)
